# untitled.net
KiCad netlist of a schematic drawn in EAGLE
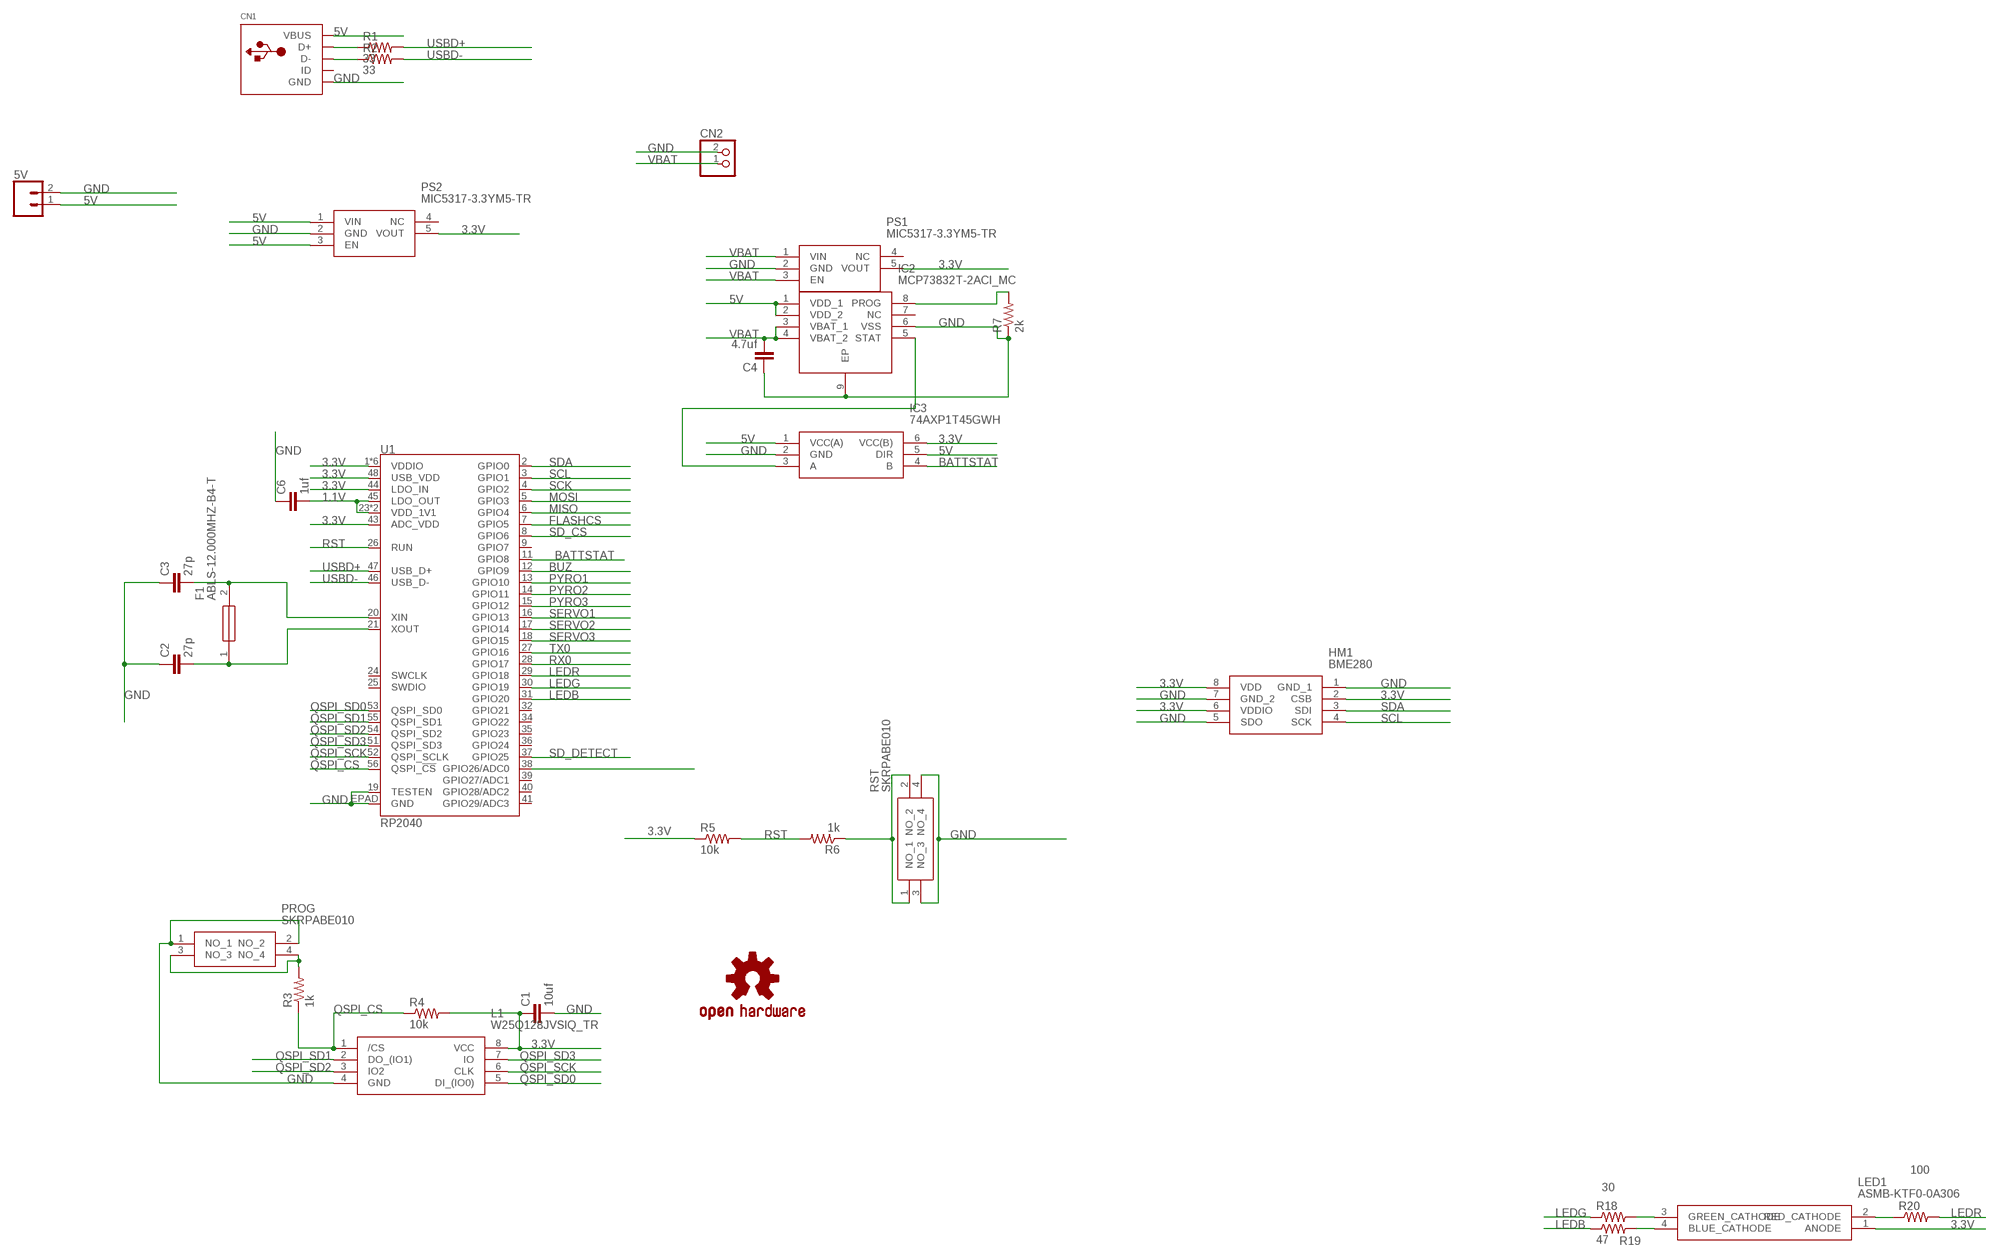
[diagram p0: schematic, sheet 1]

(export (version "E")
  (design (tool "Eeschema 10.0.6"))
  (components
    (comp (ref "5V")
      (value "CONN_02")
      (footprint "eagle-import:1X02")
      (libsource (lib "eagle-import") (part "CONN_02"))
    )
    (comp (ref "C1")
      (value "10uf")
      (footprint "eagle-import:C0805")
      (libsource (lib "eagle-import") (part "C-EUC0805"))
    )
    (comp (ref "C2")
      (value "27p")
      (footprint "eagle-import:C0805")
      (libsource (lib "eagle-import") (part "C-EUC0805"))
    )
    (comp (ref "C3")
      (value "27p")
      (footprint "eagle-import:C0805")
      (libsource (lib "eagle-import") (part "C-EUC0805"))
    )
    (comp (ref "C4")
      (value "4.7uf")
      (footprint "eagle-import:C0805")
      (libsource (lib "eagle-import") (part "C-EUC0805"))
    )
    (comp (ref "C6")
      (value "1uf")
      (footprint "eagle-import:C0805")
      (libsource (lib "eagle-import") (part "C-EUC0805"))
    )
    (comp (ref "CN1")
      (value "USBMINIB")
      (footprint "eagle-import:USB-MINIB")
      (libsource (lib "eagle-import") (part "USBMINIB"))
    )
    (comp (ref "CN2")
      (value "JST_2PIN-SMT-RA")
      (footprint "eagle-import:JST-PH-2-SMT-RA")
      (libsource (lib "eagle-import") (part "JST_2PIN-SMT-RA"))
    )
    (comp (ref "F1")
      (value "ABLS-12.000MHZ-B4-T")
      (footprint "eagle-import:HC_49US-(AT49)_1")
      (fields (field (name "MOUSER_PART_NUMBER") "815-ABLS-12.0M-T"))
      (libsource (lib "eagle-import") (part "ABLS-12.000MHZ-B4-T"))
    )
    (comp (ref "HM1")
      (value "BME280")
      (footprint "eagle-import:BME280")
      (fields (field (name "MOUSER_PART_NUMBER") "262-BME280"))
      (libsource (lib "eagle-import") (part "BME280"))
    )
    (comp (ref "IC2")
      (value "MCP73832T-2ACI_MC")
      (footprint "eagle-import:SON50P300X200X100-9N")
      (fields
        (field (name "MANUFACTURER_PART_NUMBER") "MCP73832T-2ACI/MC")
        (field (name "MOUSER_PART_NUMBER") "579-MCP73832T-2ACIMC")
      )
      (libsource (lib "eagle-import") (part "MCP73832T-2ACI_MC"))
    )
    (comp (ref "IC3")
      (value "74AXP1T45GWH")
      (footprint "eagle-import:74AXP1T45GWH")
      (fields (field (name "MOUSER_PART_NUMBER") "771-74AXP1T45GWH"))
      (libsource (lib "eagle-import") (part "74AXP1T45GWH"))
    )
    (comp (ref "L1")
      (value "W25Q128JVSIQ_TR")
      (footprint "eagle-import:SOIC127P780X195-8N")
      (fields
        (field (name "MANUFACTURER_PART_NUMBER") "W25Q128JVSIQ TR")
        (field (name "MOUSER_PART_NUMBER") "454-W25Q128JVSIQTR")
      )
      (libsource (lib "eagle-import") (part "W25Q128JVSIQ_TR"))
    )
    (comp (ref "LED1")
      (value "ASMB-KTF0-0A306")
      (footprint "eagle-import:ASMBKTF00A306")
      (fields (field (name "MOUSER_PART_NUMBER") "630-ASMB-KTF0-0A306"))
      (libsource (lib "eagle-import") (part "ASMB-KTF0-0A306"))
    )
    (comp (ref "LOGO1")
      (value "OSHW-LOGOS")
      (footprint "eagle-import:OSHW-LOGO-S")
      (libsource (lib "eagle-import") (part "OSHW-LOGOS"))
    )
    (comp (ref "PROG")
      (value "SKRPABE010")
      (footprint "eagle-import:SKRPABE010")
      (fields (field (name "MOUSER_PART_NUMBER") "688-SKRPAB"))
      (libsource (lib "eagle-import") (part "SKRPABE010"))
    )
    (comp (ref "PS1")
      (value "MIC5317-3.3YM5-TR")
      (footprint "eagle-import:SOT95P280X145-5N")
      (fields (field (name "MOUSER_PART_NUMBER") "998-MIC5317-3.3YM5TR"))
      (libsource (lib "eagle-import") (part "MIC5317-3.3YM5-TR"))
    )
    (comp (ref "PS2")
      (value "MIC5317-3.3YM5-TR")
      (footprint "eagle-import:SOT95P280X145-5N")
      (fields (field (name "MOUSER_PART_NUMBER") "998-MIC5317-3.3YM5TR"))
      (libsource (lib "eagle-import") (part "MIC5317-3.3YM5-TR"))
    )
    (comp (ref "R1")
      (value "33")
      (footprint "eagle-import:M0805")
      (libsource (lib "eagle-import") (part "R-US_M0805"))
    )
    (comp (ref "R2")
      (value "33")
      (footprint "eagle-import:M0805")
      (libsource (lib "eagle-import") (part "R-US_M0805"))
    )
    (comp (ref "R3")
      (value "1k")
      (footprint "eagle-import:M0805")
      (libsource (lib "eagle-import") (part "R-US_M0805"))
    )
    (comp (ref "R4")
      (value "10k")
      (footprint "eagle-import:M0805")
      (libsource (lib "eagle-import") (part "R-US_M0805"))
    )
    (comp (ref "R5")
      (value "10k")
      (footprint "eagle-import:M0805")
      (libsource (lib "eagle-import") (part "R-US_M0805"))
    )
    (comp (ref "R6")
      (value "1k")
      (footprint "eagle-import:M0805")
      (libsource (lib "eagle-import") (part "R-US_M0805"))
    )
    (comp (ref "R7")
      (value "2k")
      (footprint "eagle-import:M0805")
      (libsource (lib "eagle-import") (part "R-US_M0805"))
    )
    (comp (ref "R18")
      (value "30")
      (footprint "eagle-import:M0805")
      (libsource (lib "eagle-import") (part "R-US_M0805"))
    )
    (comp (ref "R19")
      (value "47")
      (footprint "eagle-import:M0805")
      (libsource (lib "eagle-import") (part "R-US_M0805"))
    )
    (comp (ref "R20")
      (value "100")
      (footprint "eagle-import:M0805")
      (libsource (lib "eagle-import") (part "R-US_M0805"))
    )
    (comp (ref "RST")
      (value "SKRPABE010")
      (footprint "eagle-import:SKRPABE010")
      (fields (field (name "MOUSER_PART_NUMBER") "688-SKRPAB"))
      (libsource (lib "eagle-import") (part "SKRPABE010"))
    )
    (comp (ref "U1")
      (value "RP2040")
      (footprint "eagle-import:QFN-56")
      (libsource (lib "eagle-import") (part "RP2040"))
    )
  )
  (nets
    (net (code "1") (name "/1.1V") (class "Default")
      (node (ref "C6") (pin "2") (pinfunction "2_2") (pintype "passive"))
      (node (ref "U1") (pin "23") (pinfunction "VDD_1V1_23") (pintype "bidirectional"))
      (node (ref "U1") (pin "45") (pinfunction "LDO_OUT_45") (pintype "bidirectional"))
      (node (ref "U1") (pin "50") (pinfunction "VDD_1V1_50") (pintype "bidirectional"))
    )
    (net (code "2") (name "/3.3V") (class "Default")
      (node (ref "C1") (pin "1") (pinfunction "1_1") (pintype "passive"))
      (node (ref "HM1") (pin "2") (pinfunction "CSB_2") (pintype "input"))
      (node (ref "HM1") (pin "6") (pinfunction "VDDIO_6") (pintype "power_in"))
      (node (ref "HM1") (pin "8") (pinfunction "VDD_8") (pintype "power_in"))
      (node (ref "IC3") (pin "6") (pinfunction "VCC(B)_6") (pintype "bidirectional"))
      (node (ref "L1") (pin "8") (pinfunction "VCC_8") (pintype "bidirectional"))
      (node (ref "LED1") (pin "1") (pinfunction "ANODE_1") (pintype "bidirectional"))
      (node (ref "PS1") (pin "5") (pinfunction "VOUT_5") (pintype "bidirectional"))
      (node (ref "PS2") (pin "5") (pinfunction "VOUT_5") (pintype "bidirectional"))
      (node (ref "R4") (pin "2") (pinfunction "2_2") (pintype "passive"))
      (node (ref "R5") (pin "1") (pinfunction "1_1") (pintype "passive"))
      (node (ref "U1") (pin "1") (pinfunction "VDDIO_1") (pintype "bidirectional"))
      (node (ref "U1") (pin "10") (pinfunction "VDDIO_10") (pintype "bidirectional"))
      (node (ref "U1") (pin "22") (pinfunction "VDDIO_22") (pintype "bidirectional"))
      (node (ref "U1") (pin "33") (pinfunction "VDDIO_33") (pintype "bidirectional"))
      (node (ref "U1") (pin "42") (pinfunction "VDDIO_42") (pintype "bidirectional"))
      (node (ref "U1") (pin "43") (pinfunction "ADC_VDD_43") (pintype "bidirectional"))
      (node (ref "U1") (pin "44") (pinfunction "LDO_IN_44") (pintype "bidirectional"))
      (node (ref "U1") (pin "48") (pinfunction "USB_VDD_48") (pintype "bidirectional"))
      (node (ref "U1") (pin "49") (pinfunction "VDDIO_49") (pintype "bidirectional"))
    )
    (net (code "3") (name "/5V") (class "Default")
      (node (ref "5V") (pin "1") (pinfunction "1_1") (pintype "passive"))
      (node (ref "CN1") (pin "VBUS") (pinfunction "VBUS_VBUS") (pintype "power_in"))
      (node (ref "IC2") (pin "1") (pinfunction "VDD_1_1") (pintype "bidirectional"))
      (node (ref "IC2") (pin "2") (pinfunction "VDD_2_2") (pintype "bidirectional"))
      (node (ref "IC3") (pin "1") (pinfunction "VCC(A)_1") (pintype "bidirectional"))
      (node (ref "IC3") (pin "5") (pinfunction "DIR_5") (pintype "bidirectional"))
      (node (ref "PS2") (pin "1") (pinfunction "VIN_1") (pintype "bidirectional"))
      (node (ref "PS2") (pin "3") (pinfunction "EN_3") (pintype "bidirectional"))
    )
    (net (code "4") (name "/BATTSTAT") (class "Default")
      (node (ref "IC3") (pin "4") (pinfunction "B_4") (pintype "bidirectional"))
      (node (ref "U1") (pin "11") (pinfunction "GPIO8_11") (pintype "bidirectional"))
    )
    (net (code "5") (name "/BUZ") (class "Default")
      (node (ref "U1") (pin "12") (pinfunction "GPIO9_12") (pintype "bidirectional"))
    )
    (net (code "6") (name "/FLASHCS") (class "Default")
      (node (ref "U1") (pin "7") (pinfunction "GPIO5_7") (pintype "bidirectional"))
    )
    (net (code "7") (name "/GND") (class "Default")
      (node (ref "5V") (pin "2") (pinfunction "2_2") (pintype "passive"))
      (node (ref "C1") (pin "2") (pinfunction "2_2") (pintype "passive"))
      (node (ref "C2") (pin "1") (pinfunction "1_1") (pintype "passive"))
      (node (ref "C3") (pin "1") (pinfunction "1_1") (pintype "passive"))
      (node (ref "C4") (pin "1") (pinfunction "1_1") (pintype "passive"))
      (node (ref "C6") (pin "1") (pinfunction "1_1") (pintype "passive"))
      (node (ref "CN1") (pin "GND") (pinfunction "GND_GND") (pintype "power_in"))
      (node (ref "CN2") (pin "2") (pinfunction "1_2") (pintype "passive"))
      (node (ref "HM1") (pin "1") (pinfunction "GND_1_1") (pintype "power_in"))
      (node (ref "HM1") (pin "5") (pinfunction "SDO_5") (pintype "bidirectional"))
      (node (ref "HM1") (pin "7") (pinfunction "GND_2_7") (pintype "power_in"))
      (node (ref "IC2") (pin "6") (pinfunction "VSS_6") (pintype "bidirectional"))
      (node (ref "IC2") (pin "9") (pinfunction "EP_9") (pintype "bidirectional"))
      (node (ref "IC3") (pin "2") (pinfunction "GND_2") (pintype "bidirectional"))
      (node (ref "L1") (pin "4") (pinfunction "GND_4") (pintype "bidirectional"))
      (node (ref "PROG") (pin "1") (pinfunction "NO_1_1") (pintype "bidirectional"))
      (node (ref "PROG") (pin "2") (pinfunction "NO_2_2") (pintype "bidirectional"))
      (node (ref "PS1") (pin "2") (pinfunction "GND_2") (pintype "bidirectional"))
      (node (ref "PS2") (pin "2") (pinfunction "GND_2") (pintype "bidirectional"))
      (node (ref "R7") (pin "1") (pinfunction "1_1") (pintype "passive"))
      (node (ref "RST") (pin "3") (pinfunction "NO_3_3") (pintype "bidirectional"))
      (node (ref "RST") (pin "4") (pinfunction "NO_4_4") (pintype "bidirectional"))
      (node (ref "U1") (pin "19") (pinfunction "TESTEN_19") (pintype "bidirectional"))
      (node (ref "U1") (pin "EPAD") (pinfunction "GND_EPAD") (pintype "bidirectional"))
    )
    (net (code "8") (name "/LEDB") (class "Default")
      (node (ref "R19") (pin "1") (pinfunction "1_1") (pintype "passive"))
      (node (ref "U1") (pin "31") (pinfunction "GPIO20_31") (pintype "bidirectional"))
    )
    (net (code "9") (name "/LEDG") (class "Default")
      (node (ref "R18") (pin "1") (pinfunction "1_1") (pintype "passive"))
      (node (ref "U1") (pin "30") (pinfunction "GPIO19_30") (pintype "bidirectional"))
    )
    (net (code "10") (name "/LEDR") (class "Default")
      (node (ref "R20") (pin "2") (pinfunction "2_2") (pintype "passive"))
      (node (ref "U1") (pin "29") (pinfunction "GPIO18_29") (pintype "bidirectional"))
    )
    (net (code "11") (name "/MISO") (class "Default")
      (node (ref "U1") (pin "6") (pinfunction "GPIO4_6") (pintype "bidirectional"))
    )
    (net (code "12") (name "/MOSI") (class "Default")
      (node (ref "U1") (pin "5") (pinfunction "GPIO3_5") (pintype "bidirectional"))
    )
    (net (code "13") (name "/PYRO1") (class "Default")
      (node (ref "U1") (pin "13") (pinfunction "GPIO10_13") (pintype "bidirectional"))
    )
    (net (code "14") (name "/PYRO2") (class "Default")
      (node (ref "U1") (pin "14") (pinfunction "GPIO11_14") (pintype "bidirectional"))
    )
    (net (code "15") (name "/PYRO3") (class "Default")
      (node (ref "U1") (pin "15") (pinfunction "GPIO12_15") (pintype "bidirectional"))
    )
    (net (code "16") (name "/QSPI_CS") (class "Default")
      (node (ref "L1") (pin "1") (pinfunction "/CS_1") (pintype "bidirectional"))
      (node (ref "R3") (pin "1") (pinfunction "1_1") (pintype "passive"))
      (node (ref "R4") (pin "1") (pinfunction "1_1") (pintype "passive"))
      (node (ref "U1") (pin "56") (pinfunction "QSPI_~{CS}_56") (pintype "bidirectional"))
    )
    (net (code "17") (name "/QSPI_SCK") (class "Default")
      (node (ref "L1") (pin "6") (pinfunction "CLK_6") (pintype "bidirectional"))
      (node (ref "U1") (pin "52") (pinfunction "QSPI_SCLK_52") (pintype "bidirectional"))
    )
    (net (code "18") (name "/QSPI_SD0") (class "Default")
      (node (ref "L1") (pin "5") (pinfunction "DI_(IO0)_5") (pintype "bidirectional"))
      (node (ref "U1") (pin "53") (pinfunction "QSPI_SD0_53") (pintype "bidirectional"))
    )
    (net (code "19") (name "/QSPI_SD1") (class "Default")
      (node (ref "L1") (pin "2") (pinfunction "DO_(IO1)_2") (pintype "bidirectional"))
      (node (ref "U1") (pin "55") (pinfunction "QSPI_SD1_55") (pintype "bidirectional"))
    )
    (net (code "20") (name "/QSPI_SD2") (class "Default")
      (node (ref "L1") (pin "3") (pinfunction "IO2_3") (pintype "bidirectional"))
      (node (ref "U1") (pin "54") (pinfunction "QSPI_SD2_54") (pintype "bidirectional"))
    )
    (net (code "21") (name "/QSPI_SD3") (class "Default")
      (node (ref "L1") (pin "7") (pinfunction "IO_7") (pintype "bidirectional"))
      (node (ref "U1") (pin "51") (pinfunction "QSPI_SD3_51") (pintype "bidirectional"))
    )
    (net (code "22") (name "/RST") (class "Default")
      (node (ref "R5") (pin "2") (pinfunction "2_2") (pintype "passive"))
      (node (ref "R6") (pin "2") (pinfunction "2_2") (pintype "passive"))
      (node (ref "U1") (pin "26") (pinfunction "RUN_26") (pintype "bidirectional"))
    )
    (net (code "23") (name "/RX0") (class "Default")
      (node (ref "U1") (pin "28") (pinfunction "GPIO17_28") (pintype "bidirectional"))
    )
    (net (code "24") (name "/SCK") (class "Default")
      (node (ref "U1") (pin "4") (pinfunction "GPIO2_4") (pintype "bidirectional"))
    )
    (net (code "25") (name "/SCL") (class "Default")
      (node (ref "HM1") (pin "4") (pinfunction "SCK_4") (pintype "bidirectional"))
      (node (ref "U1") (pin "3") (pinfunction "GPIO1_3") (pintype "bidirectional"))
    )
    (net (code "26") (name "/SDA") (class "Default")
      (node (ref "HM1") (pin "3") (pinfunction "SDI_3") (pintype "bidirectional"))
      (node (ref "U1") (pin "2") (pinfunction "GPIO0_2") (pintype "bidirectional"))
    )
    (net (code "27") (name "/SD_CS") (class "Default")
      (node (ref "U1") (pin "8") (pinfunction "GPIO6_8") (pintype "bidirectional"))
    )
    (net (code "28") (name "/SD_DETECT") (class "Default")
      (node (ref "U1") (pin "37") (pinfunction "GPIO25_37") (pintype "bidirectional"))
    )
    (net (code "29") (name "/SERVO1") (class "Default")
      (node (ref "U1") (pin "16") (pinfunction "GPIO13_16") (pintype "bidirectional"))
    )
    (net (code "30") (name "/SERVO2") (class "Default")
      (node (ref "U1") (pin "17") (pinfunction "GPIO14_17") (pintype "bidirectional"))
    )
    (net (code "31") (name "/SERVO3") (class "Default")
      (node (ref "U1") (pin "18") (pinfunction "GPIO15_18") (pintype "bidirectional"))
    )
    (net (code "32") (name "/TX0") (class "Default")
      (node (ref "U1") (pin "27") (pinfunction "GPIO16_27") (pintype "bidirectional"))
    )
    (net (code "33") (name "/USBD+") (class "Default")
      (node (ref "R1") (pin "2") (pinfunction "2_2") (pintype "passive"))
      (node (ref "U1") (pin "47") (pinfunction "USB_D+_47") (pintype "bidirectional"))
    )
    (net (code "34") (name "/USBD-") (class "Default")
      (node (ref "R2") (pin "2") (pinfunction "2_2") (pintype "passive"))
      (node (ref "U1") (pin "46") (pinfunction "USB_D-_46") (pintype "bidirectional"))
    )
    (net (code "35") (name "/VBAT") (class "Default")
      (node (ref "C4") (pin "2") (pinfunction "2_2") (pintype "passive"))
      (node (ref "CN2") (pin "1") (pinfunction "2_1") (pintype "passive"))
      (node (ref "IC2") (pin "3") (pinfunction "VBAT_1_3") (pintype "bidirectional"))
      (node (ref "IC2") (pin "4") (pinfunction "VBAT_2_4") (pintype "bidirectional"))
      (node (ref "PS1") (pin "1") (pinfunction "VIN_1") (pintype "bidirectional"))
      (node (ref "PS1") (pin "3") (pinfunction "EN_3") (pintype "bidirectional"))
    )
    (net (code "36") (name "Net-(CN1-PadD+)") (class "Default")
      (node (ref "CN1") (pin "D+") (pinfunction "D+_D+") (pintype "bidirectional"))
      (node (ref "R1") (pin "1") (pinfunction "1_1") (pintype "passive"))
    )
    (net (code "37") (name "Net-(CN1-PadD-)") (class "Default")
      (node (ref "CN1") (pin "D-") (pinfunction "D-_D-") (pintype "bidirectional"))
      (node (ref "R2") (pin "1") (pinfunction "1_1") (pintype "passive"))
    )
    (net (code "38") (name "Net-(IC2-PROG)") (class "Default")
      (node (ref "IC2") (pin "8") (pinfunction "PROG_8") (pintype "bidirectional"))
      (node (ref "R7") (pin "2") (pinfunction "2_2") (pintype "passive"))
    )
    (net (code "39") (name "Net-(IC2-STAT)") (class "Default")
      (node (ref "IC2") (pin "5") (pinfunction "STAT_5") (pintype "bidirectional"))
      (node (ref "IC3") (pin "3") (pinfunction "A_3") (pintype "bidirectional"))
    )
    (net (code "40") (name "Net-(LED1-BLUE_CATHODE)") (class "Default")
      (node (ref "LED1") (pin "4") (pinfunction "BLUE_CATHODE_4") (pintype "bidirectional"))
      (node (ref "R19") (pin "2") (pinfunction "2_2") (pintype "passive"))
    )
    (net (code "41") (name "Net-(LED1-GREEN_CATHODE)") (class "Default")
      (node (ref "LED1") (pin "3") (pinfunction "GREEN_CATHODE_3") (pintype "bidirectional"))
      (node (ref "R18") (pin "2") (pinfunction "2_2") (pintype "passive"))
    )
    (net (code "42") (name "Net-(LED1-RED_CATHODE)") (class "Default")
      (node (ref "LED1") (pin "2") (pinfunction "RED_CATHODE_2") (pintype "bidirectional"))
      (node (ref "R20") (pin "1") (pinfunction "1_1") (pintype "passive"))
    )
    (net (code "43") (name "Net-(PROG-NO_3)") (class "Default")
      (node (ref "PROG") (pin "3") (pinfunction "NO_3_3") (pintype "bidirectional"))
      (node (ref "PROG") (pin "4") (pinfunction "NO_4_4") (pintype "bidirectional"))
      (node (ref "R3") (pin "2") (pinfunction "2_2") (pintype "passive"))
    )
    (net (code "44") (name "Net-(RST-NO_1)") (class "Default")
      (node (ref "R6") (pin "1") (pinfunction "1_1") (pintype "passive"))
      (node (ref "RST") (pin "1") (pinfunction "NO_1_1") (pintype "bidirectional"))
      (node (ref "RST") (pin "2") (pinfunction "NO_2_2") (pintype "bidirectional"))
    )
    (net (code "45") (name "Net-(U1-XIN)") (class "Default")
      (node (ref "C3") (pin "2") (pinfunction "2_2") (pintype "passive"))
      (node (ref "F1") (pin "2") (pinfunction "2_2") (pintype "bidirectional"))
      (node (ref "U1") (pin "20") (pinfunction "XIN_20") (pintype "bidirectional"))
    )
    (net (code "46") (name "Net-(U1-XOUT)") (class "Default")
      (node (ref "C2") (pin "2") (pinfunction "2_2") (pintype "passive"))
      (node (ref "F1") (pin "1") (pinfunction "1_1") (pintype "bidirectional"))
      (node (ref "U1") (pin "21") (pinfunction "XOUT_21") (pintype "bidirectional"))
    )
    (net (code "47") (name "unconnected-(CN1-PadID)") (class "Default")
      (node (ref "CN1") (pin "ID") (pinfunction "ID_ID") (pintype "bidirectional"))
    )
    (net (code "48") (name "unconnected-(IC2-NC-Pad7)") (class "Default")
      (node (ref "IC2") (pin "7") (pinfunction "NC_7") (pintype "no_connect"))
    )
    (net (code "49") (name "unconnected-(PS1-NC-Pad4)") (class "Default")
      (node (ref "PS1") (pin "4") (pinfunction "NC_4") (pintype "no_connect"))
    )
    (net (code "50") (name "unconnected-(PS2-NC-Pad4)") (class "Default")
      (node (ref "PS2") (pin "4") (pinfunction "NC_4") (pintype "no_connect"))
    )
    (net (code "51") (name "unconnected-(U1-GPIO7-Pad9)") (class "Default")
      (node (ref "U1") (pin "9") (pinfunction "GPIO7_9") (pintype "bidirectional"))
    )
    (net (code "52") (name "unconnected-(U1-GPIO21-Pad32)") (class "Default")
      (node (ref "U1") (pin "32") (pinfunction "GPIO21_32") (pintype "bidirectional"))
    )
    (net (code "53") (name "unconnected-(U1-GPIO22-Pad34)") (class "Default")
      (node (ref "U1") (pin "34") (pinfunction "GPIO22_34") (pintype "bidirectional"))
    )
    (net (code "54") (name "unconnected-(U1-GPIO23-Pad35)") (class "Default")
      (node (ref "U1") (pin "35") (pinfunction "GPIO23_35") (pintype "bidirectional"))
    )
    (net (code "55") (name "unconnected-(U1-GPIO24-Pad36)") (class "Default")
      (node (ref "U1") (pin "36") (pinfunction "GPIO24_36") (pintype "bidirectional"))
    )
    (net (code "56") (name "unconnected-(U1-GPIO26{slash}ADC0-Pad38)") (class "Default")
      (node (ref "U1") (pin "38") (pinfunction "GPIO26/ADC0_38") (pintype "bidirectional"))
    )
    (net (code "57") (name "unconnected-(U1-GPIO27{slash}ADC1-Pad39)") (class "Default")
      (node (ref "U1") (pin "39") (pinfunction "GPIO27/ADC1_39") (pintype "bidirectional"))
    )
    (net (code "58") (name "unconnected-(U1-GPIO28{slash}ADC2-Pad40)") (class "Default")
      (node (ref "U1") (pin "40") (pinfunction "GPIO28/ADC2_40") (pintype "bidirectional"))
    )
    (net (code "59") (name "unconnected-(U1-GPIO29{slash}ADC3-Pad41)") (class "Default")
      (node (ref "U1") (pin "41") (pinfunction "GPIO29/ADC3_41") (pintype "bidirectional"))
    )
    (net (code "60") (name "unconnected-(U1-SWCLK-Pad24)") (class "Default")
      (node (ref "U1") (pin "24") (pinfunction "SWCLK_24") (pintype "bidirectional"))
    )
    (net (code "61") (name "unconnected-(U1-SWDIO-Pad25)") (class "Default")
      (node (ref "U1") (pin "25") (pinfunction "SWDIO_25") (pintype "bidirectional"))
    )
  )
)
